# INA219_CH1.net
KiCad netlist of a schematic drawn in Altium Designer
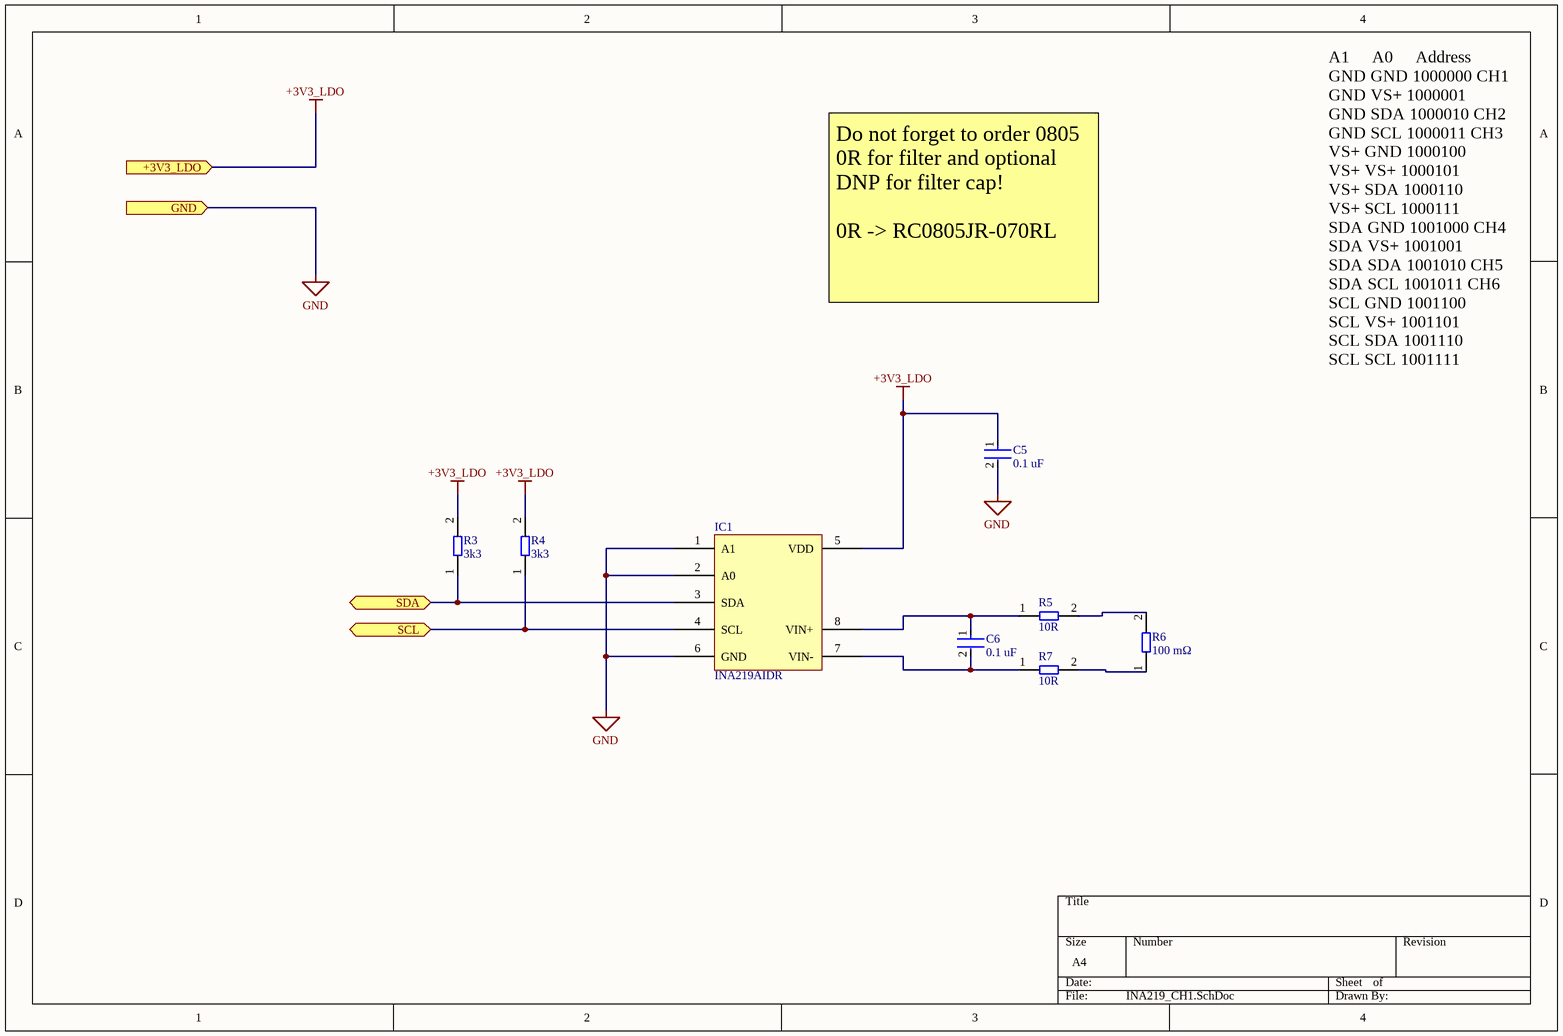
[diagram p0: INA219_CH1.SchDoc]

(export (version "E")
  (design (tool "Eeschema 10.0.6"))
  (components
    (comp (ref "C5")
      (value "0.1 uF")
      (footprint "FP-C0805C-DN-MFG")
      (description "C0805 0.10 μF X7R 30ppm/°C 20.00% 50 V C0805C104M5RAC")
      (fields
        (field (name "MANUFACTURER PART NUMBER") "C0805C104M5RAC")
        (field (name "MANUFACTURER") "KEMET")
      )
      (libsource (lib "Altium Content Vault") (part "b4654b650e69147ec39a6b967a45e02"))
    )
    (comp (ref "C6")
      (value "0.1 uF")
      (footprint "FP-C0805C-DN-MFG")
      (description "C0805 0.10 μF X7R 30ppm/°C 20.00% 50 V C0805C104M5RAC")
      (fields
        (field (name "MANUFACTURER PART NUMBER") "C0805C104M5RAC")
        (field (name "MANUFACTURER") "KEMET")
      )
      (libsource (lib "Altium Content Vault") (part "b4654b650e69147ec39a6b967a45e02"))
    )
    (comp (ref "IC1")
      (value "INA219AIDR")
      (footprint "INA219AIDR")
      (description "Current & Power Monitors & Regulators Zero-Drift,Bi-Dir Crnt/Pwr Monitor")
      (libsource (lib "Callisto Control Board") (part "INA219AIDR"))
    )
    (comp (ref "R3")
      (value "3k3")
      (footprint "0805 Resistor - IPC A")
      (description "Thick Film Resistors - SMD 3.3 kOhms 125 mW 0805 1%\r\nRE0805FRE073K3L")
      (libsource (lib "Callisto Control Board") (part "RE0805FRE073K3L"))
    )
    (comp (ref "R4")
      (value "3k3")
      (footprint "0805 Resistor - IPC A")
      (description "Thick Film Resistors - SMD 3.3 kOhms 125 mW 0805 1%\r\nRE0805FRE073K3L")
      (libsource (lib "Callisto Control Board") (part "RE0805FRE073K3L"))
    )
    (comp (ref "R5")
      (value "10R")
      (footprint "0805 Resistor - IPC A")
      (description "Thick Film Resistors - SMD 10 Ohms 125 mW 0805 1%\r\nRC0805FR-0710RL")
      (libsource (lib "Callisto Control Board") (part "RC0805FR-0710RL"))
    )
    (comp (ref "R6")
      (value "100 mΩ")
      (footprint "PE2512FKM070R1L")
      (description "Current Sense Resistors - SMD 100 mOhms 1 Watt 1 % 75 ppm/C AEC-Q200\r\nPE2512FKM070R1L")
      (libsource (lib "Callisto Control Board") (part "PE2512FKM070R1L"))
    )
    (comp (ref "R7")
      (value "10R")
      (footprint "0805 Resistor - IPC A")
      (description "Thick Film Resistors - SMD 10 Ohms 125 mW 0805 1%\r\nRC0805FR-0710RL")
      (libsource (lib "Callisto Control Board") (part "RC0805FR-0710RL"))
    )
  )
  (nets
    (net (code "1") (name "+3V3_LDO") (class "Default")
      (node (ref "C5") (pin "1") (pinfunction "1_1") (pintype "passive"))
      (node (ref "IC1") (pin "5") (pinfunction "VDD_5") (pintype "passive"))
      (node (ref "R3") (pin "2") (pintype "passive"))
      (node (ref "R4") (pin "2") (pintype "passive"))
    )
    (net (code "2") (name "/SCL") (class "Default")
      (node (ref "IC1") (pin "4") (pinfunction "SCL_4") (pintype "passive"))
      (node (ref "R4") (pin "1") (pintype "passive"))
    )
    (net (code "3") (name "/SDA") (class "Default")
      (node (ref "IC1") (pin "3") (pinfunction "SDA_3") (pintype "passive"))
      (node (ref "R3") (pin "1") (pintype "passive"))
    )
    (net (code "4") (name "GND") (class "Default")
      (node (ref "C5") (pin "2") (pinfunction "2_2") (pintype "passive"))
      (node (ref "IC1") (pin "1") (pinfunction "A1_1") (pintype "passive"))
      (node (ref "IC1") (pin "2") (pinfunction "A0_2") (pintype "passive"))
      (node (ref "IC1") (pin "6") (pinfunction "GND_6") (pintype "passive"))
    )
    (net (code "5") (name "Net-(IC1-VIN+)") (class "Default")
      (node (ref "C6") (pin "1") (pinfunction "1_1") (pintype "passive"))
      (node (ref "IC1") (pin "8") (pinfunction "VIN+_8") (pintype "passive"))
      (node (ref "R5") (pin "1") (pintype "passive"))
    )
    (net (code "6") (name "Net-(IC1-VIN-)") (class "Default")
      (node (ref "C6") (pin "2") (pinfunction "2_2") (pintype "passive"))
      (node (ref "IC1") (pin "7") (pinfunction "VIN-_7") (pintype "passive"))
      (node (ref "R7") (pin "1") (pintype "passive"))
    )
    (net (code "7") (name "Net-(R5-Pad2)") (class "Default")
      (node (ref "R5") (pin "2") (pintype "passive"))
      (node (ref "R6") (pin "2") (pintype "passive"))
    )
    (net (code "8") (name "Net-(R6-Pad1)") (class "Default")
      (node (ref "R6") (pin "1") (pintype "passive"))
      (node (ref "R7") (pin "2") (pintype "passive"))
    )
  )
)
